# Integration_board_3008.net
KiCad netlist of a schematic drawn in EAGLE
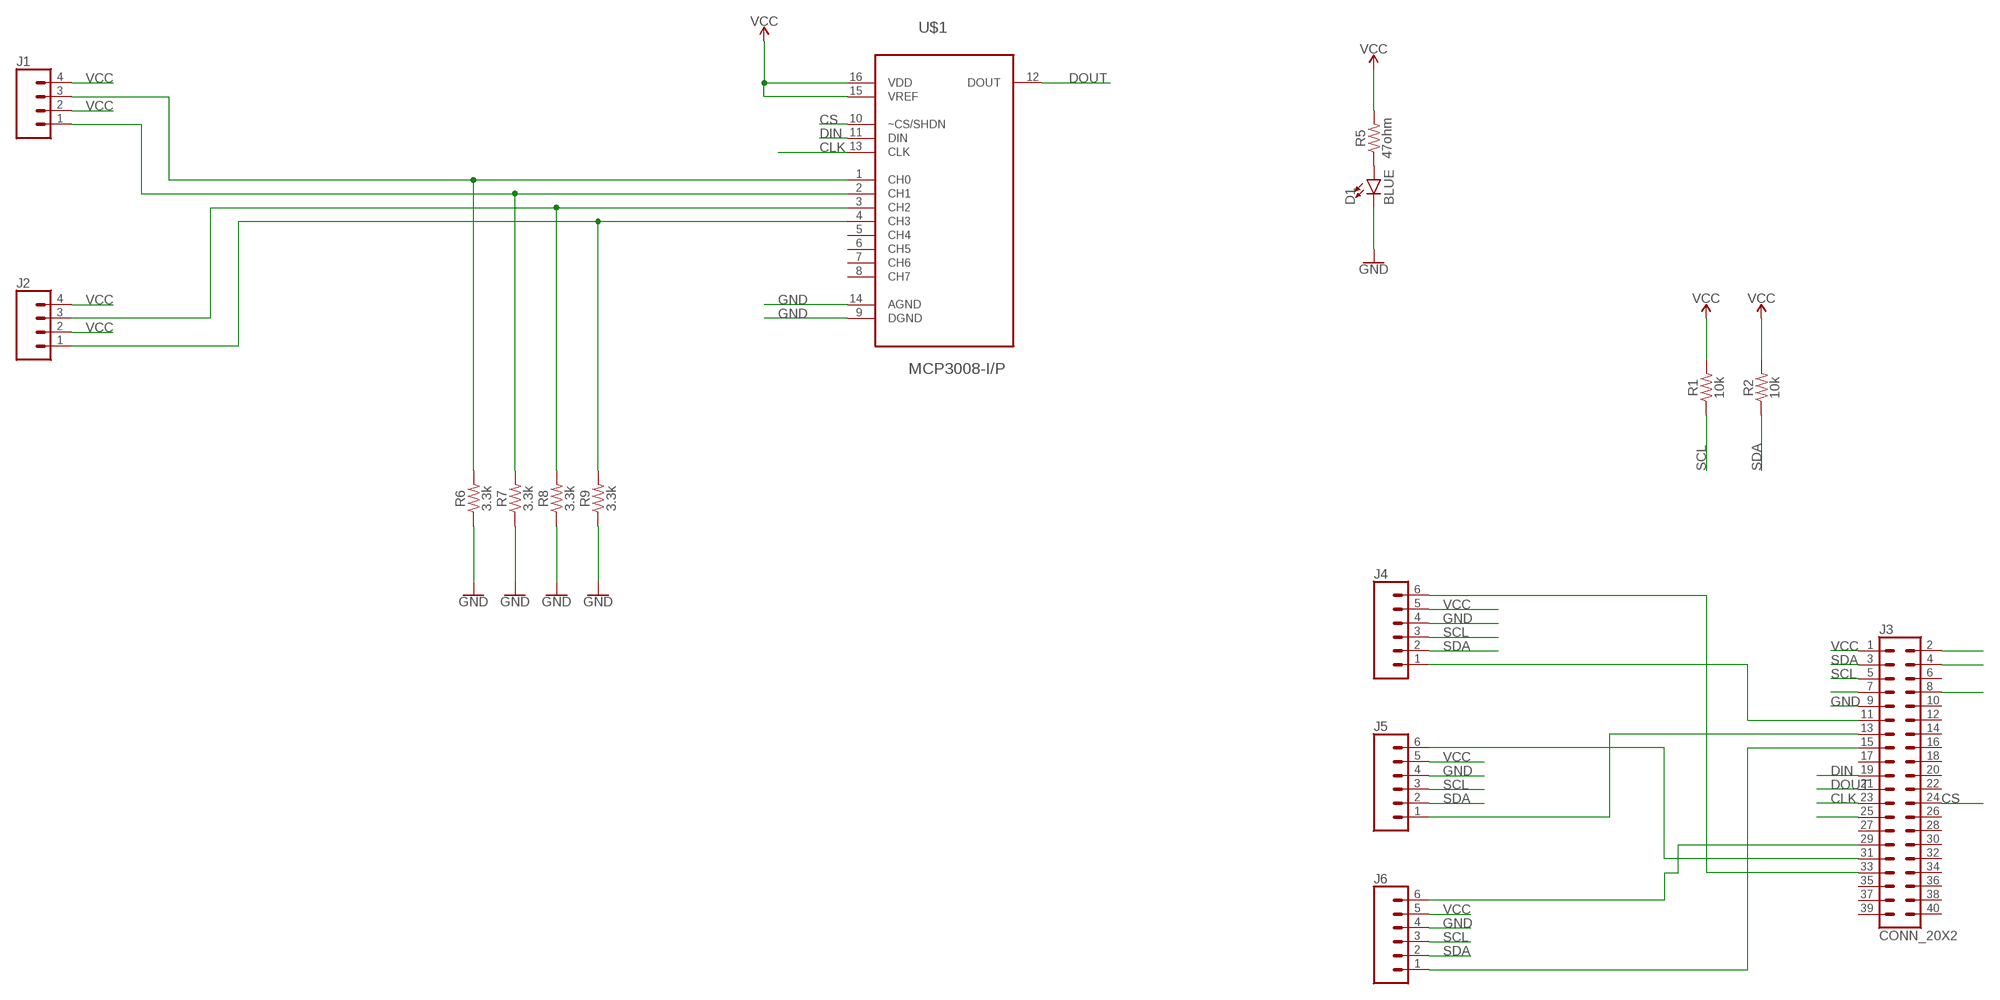
[diagram p0: schematic, sheet 1]

(export (version "E")
  (design (tool "Eeschema 10.0.6"))
  (components
    (comp (ref "D1")
      (value "BLUE")
      (footprint "eagle-import:LED-0603")
      (libsource (lib "eagle-import") (part "LED-BLUE0603"))
    )
    (comp (ref "J1")
      (value "CONN_04PTH")
      (footprint "eagle-import:1X04")
      (libsource (lib "eagle-import") (part "CONN_04PTH"))
    )
    (comp (ref "J2")
      (value "CONN_04PTH")
      (footprint "eagle-import:1X04")
      (libsource (lib "eagle-import") (part "CONN_04PTH"))
    )
    (comp (ref "J3")
      (value "CONN_20X2")
      (footprint "eagle-import:2X20")
      (libsource (lib "eagle-import") (part "CONN_20X2"))
    )
    (comp (ref "J4")
      (value "CONN_06SILK_FEMALE_PTH")
      (footprint "eagle-import:1X06")
      (libsource (lib "eagle-import") (part "CONN_06SILK_FEMALE_PTH"))
    )
    (comp (ref "J5")
      (value "CONN_06SILK_FEMALE_PTH")
      (footprint "eagle-import:1X06")
      (libsource (lib "eagle-import") (part "CONN_06SILK_FEMALE_PTH"))
    )
    (comp (ref "J6")
      (value "CONN_06SILK_FEMALE_PTH")
      (footprint "eagle-import:1X06")
      (libsource (lib "eagle-import") (part "CONN_06SILK_FEMALE_PTH"))
    )
    (comp (ref "R1")
      (value "10k")
      (footprint "eagle-import:0805")
      (libsource (lib "eagle-import") (part "RESISTOR0805"))
    )
    (comp (ref "R2")
      (value "10k")
      (footprint "eagle-import:0805")
      (libsource (lib "eagle-import") (part "RESISTOR0805"))
    )
    (comp (ref "R5")
      (value "47ohm")
      (footprint "eagle-import:0805")
      (libsource (lib "eagle-import") (part "RESISTOR0805"))
    )
    (comp (ref "R6")
      (value "3.3k")
      (footprint "eagle-import:0805")
      (libsource (lib "eagle-import") (part "RESISTOR0805"))
    )
    (comp (ref "R7")
      (value "3.3k")
      (footprint "eagle-import:0805")
      (libsource (lib "eagle-import") (part "RESISTOR0805"))
    )
    (comp (ref "R8")
      (value "3.3k")
      (footprint "eagle-import:0805")
      (libsource (lib "eagle-import") (part "RESISTOR0805"))
    )
    (comp (ref "R9")
      (value "3.3k")
      (footprint "eagle-import:0805")
      (libsource (lib "eagle-import") (part "RESISTOR0805"))
    )
    (comp (ref "U$1")
      (value "MCP3008-I/P")
      (footprint "eagle-import:DIP254P762X432-16")
      (libsource (lib "eagle-import") (part "MCP3008-I/P"))
    )
  )
  (nets
    (net (code "1") (name "/CLK") (class "Default")
      (node (ref "J3") (pin "23") (pinfunction "23_23") (pintype "passive"))
      (node (ref "U$1") (pin "13") (pinfunction "CLK_13") (pintype "input"))
    )
    (net (code "2") (name "/CS") (class "Default")
      (node (ref "J3") (pin "24") (pinfunction "24_24") (pintype "passive"))
      (node (ref "U$1") (pin "10") (pinfunction "~{CS/SHDN}_10") (pintype "input"))
    )
    (net (code "3") (name "/DIN") (class "Default")
      (node (ref "J3") (pin "19") (pinfunction "19_19") (pintype "passive"))
      (node (ref "U$1") (pin "11") (pinfunction "DIN_11") (pintype "input"))
    )
    (net (code "4") (name "/DOUT") (class "Default")
      (node (ref "J3") (pin "21") (pinfunction "21_21") (pintype "passive"))
      (node (ref "U$1") (pin "12") (pinfunction "DOUT_12") (pintype "output"))
    )
    (net (code "5") (name "/SCL") (class "Default")
      (node (ref "J3") (pin "5") (pinfunction "5_5") (pintype "passive"))
      (node (ref "J4") (pin "3") (pinfunction "3_3") (pintype "passive"))
      (node (ref "J5") (pin "3") (pinfunction "3_3") (pintype "passive"))
      (node (ref "J6") (pin "3") (pinfunction "3_3") (pintype "passive"))
      (node (ref "R1") (pin "1") (pinfunction "1_1") (pintype "passive"))
    )
    (net (code "6") (name "/SDA") (class "Default")
      (node (ref "J3") (pin "3") (pinfunction "3_3") (pintype "passive"))
      (node (ref "J4") (pin "2") (pinfunction "2_2") (pintype "passive"))
      (node (ref "J5") (pin "2") (pinfunction "2_2") (pintype "passive"))
      (node (ref "J6") (pin "2") (pinfunction "2_2") (pintype "passive"))
      (node (ref "R2") (pin "1") (pinfunction "1_1") (pintype "passive"))
    )
    (net (code "7") (name "GND") (class "Default")
      (node (ref "D1") (pin "C") (pinfunction "C_C") (pintype "passive"))
      (node (ref "J3") (pin "9") (pinfunction "9_9") (pintype "passive"))
      (node (ref "J4") (pin "4") (pinfunction "4_4") (pintype "passive"))
      (node (ref "J5") (pin "4") (pinfunction "4_4") (pintype "passive"))
      (node (ref "J6") (pin "4") (pinfunction "4_4") (pintype "passive"))
      (node (ref "R6") (pin "1") (pinfunction "1_1") (pintype "passive"))
      (node (ref "R7") (pin "1") (pinfunction "1_1") (pintype "passive"))
      (node (ref "R8") (pin "1") (pinfunction "1_1") (pintype "passive"))
      (node (ref "R9") (pin "1") (pinfunction "1_1") (pintype "passive"))
      (node (ref "U$1") (pin "14") (pinfunction "AGND_14") (pintype "passive"))
      (node (ref "U$1") (pin "9") (pinfunction "DGND_9") (pintype "passive"))
    )
    (net (code "8") (name "Net-(D1-PadA)") (class "Default")
      (node (ref "D1") (pin "A") (pinfunction "A_A") (pintype "passive"))
      (node (ref "R5") (pin "1") (pinfunction "1_1") (pintype "passive"))
    )
    (net (code "9") (name "Net-(J3-Pad11)") (class "Default")
      (node (ref "J3") (pin "11") (pinfunction "11_11") (pintype "passive"))
      (node (ref "J4") (pin "1") (pinfunction "1_1") (pintype "passive"))
    )
    (net (code "10") (name "Net-(J3-Pad13)") (class "Default")
      (node (ref "J3") (pin "13") (pinfunction "13_13") (pintype "passive"))
      (node (ref "J5") (pin "1") (pinfunction "1_1") (pintype "passive"))
    )
    (net (code "11") (name "Net-(J3-Pad15)") (class "Default")
      (node (ref "J3") (pin "15") (pinfunction "15_15") (pintype "passive"))
      (node (ref "J6") (pin "1") (pinfunction "1_1") (pintype "passive"))
    )
    (net (code "12") (name "Net-(J3-Pad29)") (class "Default")
      (node (ref "J3") (pin "29") (pinfunction "29_29") (pintype "passive"))
      (node (ref "J6") (pin "6") (pinfunction "6_6") (pintype "passive"))
    )
    (net (code "13") (name "Net-(J3-Pad31)") (class "Default")
      (node (ref "J3") (pin "31") (pinfunction "31_31") (pintype "passive"))
      (node (ref "J5") (pin "6") (pinfunction "6_6") (pintype "passive"))
    )
    (net (code "14") (name "Net-(J3-Pad33)") (class "Default")
      (node (ref "J3") (pin "33") (pinfunction "33_33") (pintype "passive"))
      (node (ref "J4") (pin "6") (pinfunction "6_6") (pintype "passive"))
    )
    (net (code "15") (name "Net-(U$1-CH0)") (class "Default")
      (node (ref "J1") (pin "3") (pinfunction "3_3") (pintype "passive"))
      (node (ref "R6") (pin "2") (pinfunction "2_2") (pintype "passive"))
      (node (ref "U$1") (pin "1") (pinfunction "CH0_1") (pintype "input"))
    )
    (net (code "16") (name "Net-(U$1-CH1)") (class "Default")
      (node (ref "J1") (pin "1") (pinfunction "1_1") (pintype "passive"))
      (node (ref "R7") (pin "2") (pinfunction "2_2") (pintype "passive"))
      (node (ref "U$1") (pin "2") (pinfunction "CH1_2") (pintype "input"))
    )
    (net (code "17") (name "Net-(U$1-CH2)") (class "Default")
      (node (ref "J2") (pin "3") (pinfunction "3_3") (pintype "passive"))
      (node (ref "R8") (pin "2") (pinfunction "2_2") (pintype "passive"))
      (node (ref "U$1") (pin "3") (pinfunction "CH2_3") (pintype "input"))
    )
    (net (code "18") (name "Net-(U$1-CH3)") (class "Default")
      (node (ref "J2") (pin "1") (pinfunction "1_1") (pintype "passive"))
      (node (ref "R9") (pin "2") (pinfunction "2_2") (pintype "passive"))
      (node (ref "U$1") (pin "4") (pinfunction "CH3_4") (pintype "input"))
    )
    (net (code "19") (name "VCC") (class "Default")
      (node (ref "J1") (pin "2") (pinfunction "2_2") (pintype "passive"))
      (node (ref "J1") (pin "4") (pinfunction "4_4") (pintype "passive"))
      (node (ref "J2") (pin "2") (pinfunction "2_2") (pintype "passive"))
      (node (ref "J2") (pin "4") (pinfunction "4_4") (pintype "passive"))
      (node (ref "J3") (pin "1") (pinfunction "1_1") (pintype "passive"))
      (node (ref "J4") (pin "5") (pinfunction "5_5") (pintype "passive"))
      (node (ref "J5") (pin "5") (pinfunction "5_5") (pintype "passive"))
      (node (ref "J6") (pin "5") (pinfunction "5_5") (pintype "passive"))
      (node (ref "R1") (pin "2") (pinfunction "2_2") (pintype "passive"))
      (node (ref "R2") (pin "2") (pinfunction "2_2") (pintype "passive"))
      (node (ref "R5") (pin "2") (pinfunction "2_2") (pintype "passive"))
      (node (ref "U$1") (pin "15") (pinfunction "VREF_15") (pintype "power_in"))
      (node (ref "U$1") (pin "16") (pinfunction "VDD_16") (pintype "power_in"))
    )
    (net (code "20") (name "unconnected-(J3-Pad2)") (class "Default")
      (node (ref "J3") (pin "2") (pinfunction "2_2") (pintype "passive"))
    )
    (net (code "21") (name "unconnected-(J3-Pad4)") (class "Default")
      (node (ref "J3") (pin "4") (pinfunction "4_4") (pintype "passive"))
    )
    (net (code "22") (name "unconnected-(J3-Pad6)") (class "Default")
      (node (ref "J3") (pin "6") (pinfunction "6_6") (pintype "passive"))
    )
    (net (code "23") (name "unconnected-(J3-Pad7)") (class "Default")
      (node (ref "J3") (pin "7") (pinfunction "7_7") (pintype "passive"))
    )
    (net (code "24") (name "unconnected-(J3-Pad8)") (class "Default")
      (node (ref "J3") (pin "8") (pinfunction "8_8") (pintype "passive"))
    )
    (net (code "25") (name "unconnected-(J3-Pad10)") (class "Default")
      (node (ref "J3") (pin "10") (pinfunction "10_10") (pintype "passive"))
    )
    (net (code "26") (name "unconnected-(J3-Pad12)") (class "Default")
      (node (ref "J3") (pin "12") (pinfunction "12_12") (pintype "passive"))
    )
    (net (code "27") (name "unconnected-(J3-Pad14)") (class "Default")
      (node (ref "J3") (pin "14") (pinfunction "14_14") (pintype "passive"))
    )
    (net (code "28") (name "unconnected-(J3-Pad16)") (class "Default")
      (node (ref "J3") (pin "16") (pinfunction "16_16") (pintype "passive"))
    )
    (net (code "29") (name "unconnected-(J3-Pad17)") (class "Default")
      (node (ref "J3") (pin "17") (pinfunction "17_17") (pintype "passive"))
    )
    (net (code "30") (name "unconnected-(J3-Pad18)") (class "Default")
      (node (ref "J3") (pin "18") (pinfunction "18_18") (pintype "passive"))
    )
    (net (code "31") (name "unconnected-(J3-Pad20)") (class "Default")
      (node (ref "J3") (pin "20") (pinfunction "20_20") (pintype "passive"))
    )
    (net (code "32") (name "unconnected-(J3-Pad22)") (class "Default")
      (node (ref "J3") (pin "22") (pinfunction "22_22") (pintype "passive"))
    )
    (net (code "33") (name "unconnected-(J3-Pad25)") (class "Default")
      (node (ref "J3") (pin "25") (pinfunction "25_25") (pintype "passive"))
    )
    (net (code "34") (name "unconnected-(J3-Pad26)") (class "Default")
      (node (ref "J3") (pin "26") (pinfunction "26_26") (pintype "passive"))
    )
    (net (code "35") (name "unconnected-(J3-Pad27)") (class "Default")
      (node (ref "J3") (pin "27") (pinfunction "27_27") (pintype "passive"))
    )
    (net (code "36") (name "unconnected-(J3-Pad28)") (class "Default")
      (node (ref "J3") (pin "28") (pinfunction "28_28") (pintype "passive"))
    )
    (net (code "37") (name "unconnected-(J3-Pad30)") (class "Default")
      (node (ref "J3") (pin "30") (pinfunction "30_30") (pintype "passive"))
    )
    (net (code "38") (name "unconnected-(J3-Pad32)") (class "Default")
      (node (ref "J3") (pin "32") (pinfunction "32_32") (pintype "passive"))
    )
    (net (code "39") (name "unconnected-(J3-Pad34)") (class "Default")
      (node (ref "J3") (pin "34") (pinfunction "34_34") (pintype "passive"))
    )
    (net (code "40") (name "unconnected-(J3-Pad35)") (class "Default")
      (node (ref "J3") (pin "35") (pinfunction "35_35") (pintype "passive"))
    )
    (net (code "41") (name "unconnected-(J3-Pad36)") (class "Default")
      (node (ref "J3") (pin "36") (pinfunction "36_36") (pintype "passive"))
    )
    (net (code "42") (name "unconnected-(J3-Pad37)") (class "Default")
      (node (ref "J3") (pin "37") (pinfunction "37_37") (pintype "passive"))
    )
    (net (code "43") (name "unconnected-(J3-Pad38)") (class "Default")
      (node (ref "J3") (pin "38") (pinfunction "38_38") (pintype "passive"))
    )
    (net (code "44") (name "unconnected-(J3-Pad39)") (class "Default")
      (node (ref "J3") (pin "39") (pinfunction "39_39") (pintype "passive"))
    )
    (net (code "45") (name "unconnected-(J3-Pad40)") (class "Default")
      (node (ref "J3") (pin "40") (pinfunction "40_40") (pintype "passive"))
    )
    (net (code "46") (name "unconnected-(U$1-CH4-Pad5)") (class "Default")
      (node (ref "U$1") (pin "5") (pinfunction "CH4_5") (pintype "input"))
    )
    (net (code "47") (name "unconnected-(U$1-CH5-Pad6)") (class "Default")
      (node (ref "U$1") (pin "6") (pinfunction "CH5_6") (pintype "input"))
    )
    (net (code "48") (name "unconnected-(U$1-CH6-Pad7)") (class "Default")
      (node (ref "U$1") (pin "7") (pinfunction "CH6_7") (pintype "input"))
    )
    (net (code "49") (name "unconnected-(U$1-CH7-Pad8)") (class "Default")
      (node (ref "U$1") (pin "8") (pinfunction "CH7_8") (pintype "input"))
    )
  )
)
